# nlp_base.net
KiCad netlist of a schematic drawn in EasyEDA
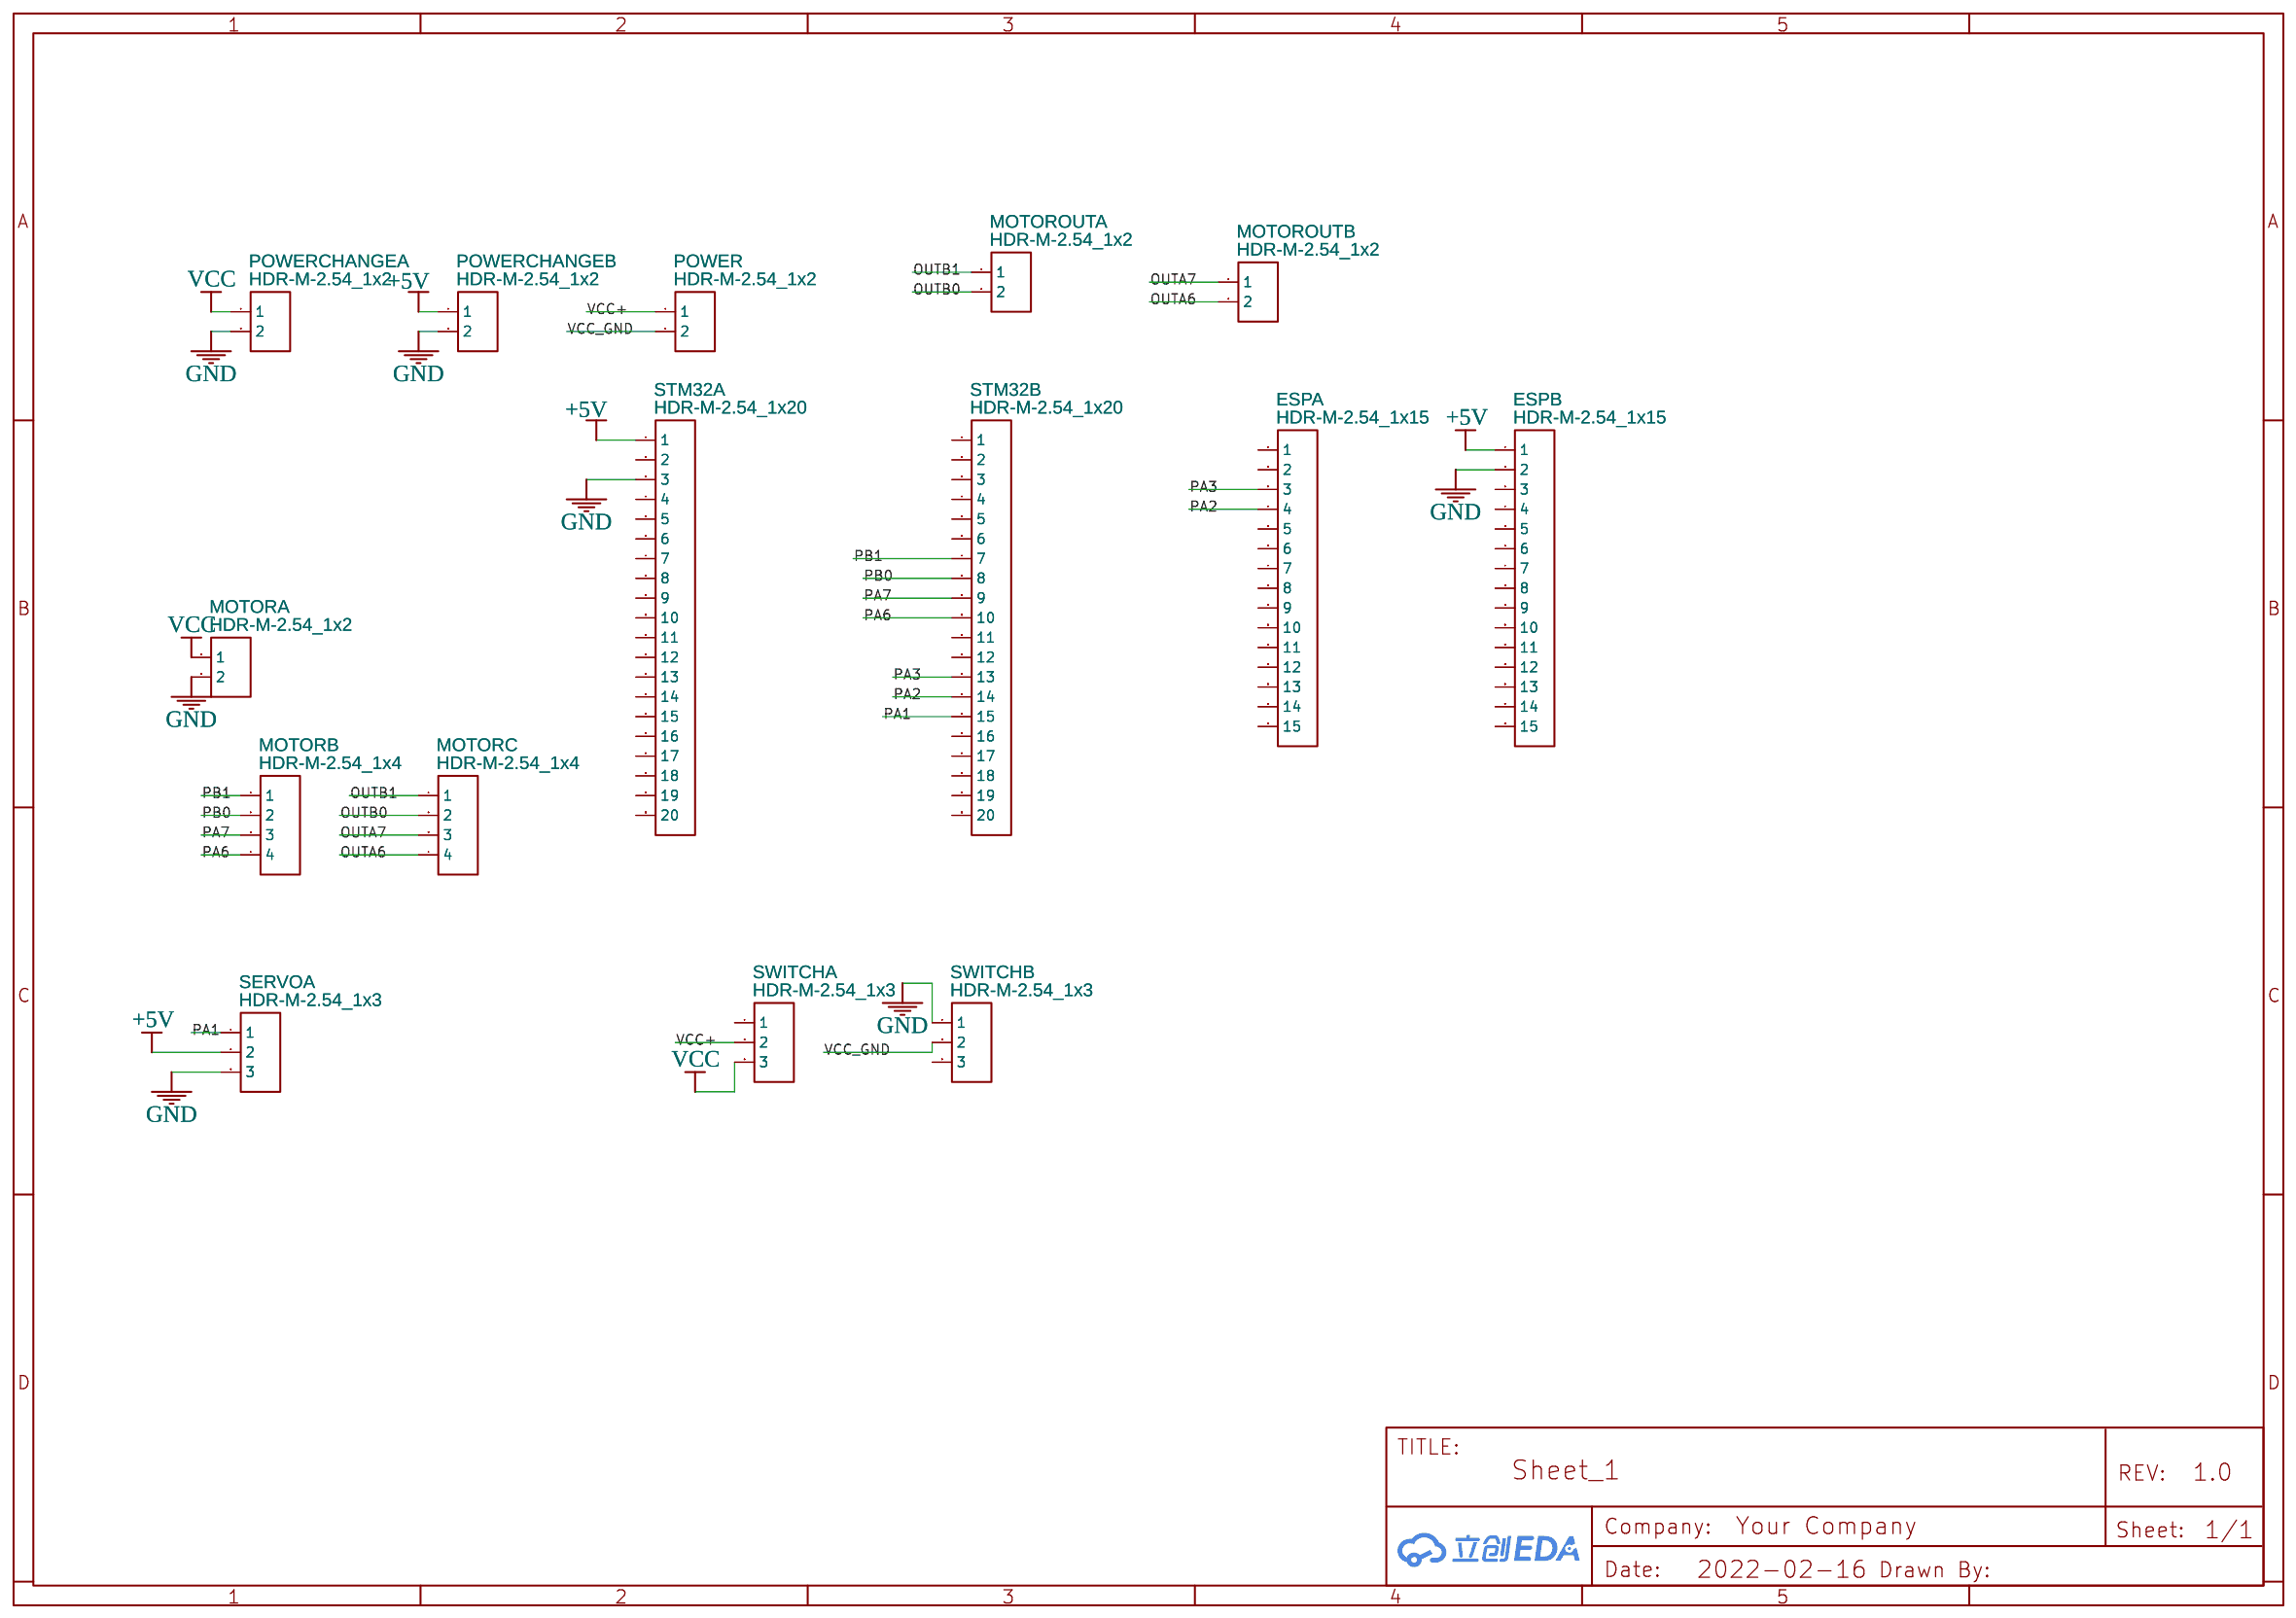
[diagram p0: schematic sheet]

(export (version "E")
  (design (tool "Eeschema 10.0.6"))
  (components
    (comp (ref "ESPA")
      (value "HDR-M-2.54_1x15")
      (fields (field (name "BOM_Supplier Part") "C124373"))
      (libsource (lib "") (part "HDR-M-2.54_1x15_1"))
    )
    (comp (ref "ESPB")
      (value "HDR-M-2.54_1x15")
      (fields (field (name "BOM_Supplier Part") "C124373"))
      (libsource (lib "") (part "HDR-M-2.54_1x15"))
    )
    (comp (ref "MOTORA")
      (value "HDR-M-2.54_1x2")
      (fields (field (name "BOM_Supplier Part") "C124375"))
      (libsource (lib "") (part "HDR-M-2.54_1x2_1"))
    )
    (comp (ref "MOTORB")
      (value "HDR-M-2.54_1x4")
      (fields (field (name "BOM_Supplier Part") "C124378"))
      (libsource (lib "") (part "HDR-M-2.54_1x4_1"))
    )
    (comp (ref "MOTORC")
      (value "HDR-M-2.54_1x4")
      (fields (field (name "BOM_Supplier Part") "C124378"))
      (libsource (lib "") (part "HDR-M-2.54_1x4"))
    )
    (comp (ref "MOTOROUTA")
      (value "HDR-M-2.54_1x2")
      (fields (field (name "BOM_Supplier Part") "C124375"))
      (libsource (lib "") (part "HDR-M-2.54_1x2_3"))
    )
    (comp (ref "MOTOROUTB")
      (value "HDR-M-2.54_1x2")
      (fields (field (name "BOM_Supplier Part") "C124375"))
      (libsource (lib "") (part "HDR-M-2.54_1x2_4"))
    )
    (comp (ref "POWER")
      (value "HDR-M-2.54_1x2")
      (fields (field (name "BOM_Supplier Part") "C124375"))
      (libsource (lib "") (part "HDR-M-2.54_1x2_2"))
    )
    (comp (ref "POWERCHANGEA")
      (value "HDR-M-2.54_1x2")
      (fields (field (name "BOM_Supplier Part") "C124375"))
      (libsource (lib "") (part "HDR-M-2.54_1x2"))
    )
    (comp (ref "POWERCHANGEB")
      (value "HDR-M-2.54_1x2")
      (fields (field (name "BOM_Supplier Part") "C124375"))
      (libsource (lib "") (part "HDR-M-2.54_1x2_5"))
    )
    (comp (ref "SERVOA")
      (value "HDR-M-2.54_1x3")
      (fields (field (name "BOM_Supplier Part") "C180248"))
      (libsource (lib "") (part "HDR-M-2.54_1x3_2"))
    )
    (comp (ref "STM32A")
      (value "HDR-M-2.54_1x20")
      (fields (field (name "BOM_Supplier Part") "C50981"))
      (libsource (lib "") (part "HDR-M-2.54_1x20_1"))
    )
    (comp (ref "STM32B")
      (value "HDR-M-2.54_1x20")
      (fields (field (name "BOM_Supplier Part") "C50981"))
      (libsource (lib "") (part "HDR-M-2.54_1x20"))
    )
    (comp (ref "SWITCHA")
      (value "HDR-M-2.54_1x3")
      (fields (field (name "BOM_Supplier Part") "C180248"))
      (libsource (lib "") (part "HDR-M-2.54_1x3_1"))
    )
    (comp (ref "SWITCHB")
      (value "HDR-M-2.54_1x3")
      (fields (field (name "BOM_Supplier Part") "C180248"))
      (libsource (lib "") (part "HDR-M-2.54_1x3"))
    )
  )
  (nets
    (net (code "1") (name "+5V") (class "Default")
      (node (ref "ESPB") (pin "1") (pinfunction "1_1") (pintype "unspecified"))
      (node (ref "POWERCHANGEB") (pin "1") (pinfunction "1_1") (pintype "unspecified"))
      (node (ref "SERVOA") (pin "2") (pinfunction "2_2") (pintype "input"))
      (node (ref "STM32A") (pin "1") (pinfunction "1_1") (pintype "unspecified"))
    )
    (net (code "2") (name "/OUTA6") (class "Default")
      (node (ref "MOTORC") (pin "4") (pinfunction "4_4") (pintype "unspecified"))
      (node (ref "MOTOROUTB") (pin "2") (pinfunction "2_2") (pintype "unspecified"))
    )
    (net (code "3") (name "/OUTA7") (class "Default")
      (node (ref "MOTORC") (pin "3") (pinfunction "3_3") (pintype "unspecified"))
      (node (ref "MOTOROUTB") (pin "1") (pinfunction "1_1") (pintype "unspecified"))
    )
    (net (code "4") (name "/OUTB0") (class "Default")
      (node (ref "MOTORC") (pin "2") (pinfunction "2_2") (pintype "unspecified"))
      (node (ref "MOTOROUTA") (pin "2") (pinfunction "2_2") (pintype "unspecified"))
    )
    (net (code "5") (name "/OUTB1") (class "Default")
      (node (ref "MOTORC") (pin "1") (pinfunction "1_1") (pintype "unspecified"))
      (node (ref "MOTOROUTA") (pin "1") (pinfunction "1_1") (pintype "unspecified"))
    )
    (net (code "6") (name "/PA1") (class "Default")
      (node (ref "SERVOA") (pin "1") (pinfunction "1_1") (pintype "input"))
      (node (ref "STM32B") (pin "15") (pinfunction "15_15") (pintype "unspecified"))
    )
    (net (code "7") (name "/PA2") (class "Default")
      (node (ref "ESPA") (pin "4") (pinfunction "4_4") (pintype "unspecified"))
      (node (ref "STM32B") (pin "14") (pinfunction "14_14") (pintype "unspecified"))
    )
    (net (code "8") (name "/PA3") (class "Default")
      (node (ref "ESPA") (pin "3") (pinfunction "3_3") (pintype "unspecified"))
      (node (ref "STM32B") (pin "13") (pinfunction "13_13") (pintype "unspecified"))
    )
    (net (code "9") (name "/PA6") (class "Default")
      (node (ref "MOTORB") (pin "4") (pinfunction "4_4") (pintype "unspecified"))
      (node (ref "STM32B") (pin "10") (pinfunction "10_10") (pintype "unspecified"))
    )
    (net (code "10") (name "/PA7") (class "Default")
      (node (ref "MOTORB") (pin "3") (pinfunction "3_3") (pintype "unspecified"))
      (node (ref "STM32B") (pin "9") (pinfunction "9_9") (pintype "unspecified"))
    )
    (net (code "11") (name "/PB0") (class "Default")
      (node (ref "MOTORB") (pin "2") (pinfunction "2_2") (pintype "unspecified"))
      (node (ref "STM32B") (pin "8") (pinfunction "8_8") (pintype "unspecified"))
    )
    (net (code "12") (name "/PB1") (class "Default")
      (node (ref "MOTORB") (pin "1") (pinfunction "1_1") (pintype "unspecified"))
      (node (ref "STM32B") (pin "7") (pinfunction "7_7") (pintype "unspecified"))
    )
    (net (code "13") (name "/VCC+") (class "Default")
      (node (ref "POWER") (pin "1") (pinfunction "1_1") (pintype "unspecified"))
      (node (ref "SWITCHA") (pin "2") (pinfunction "2_2") (pintype "input"))
    )
    (net (code "14") (name "/VCC_GND") (class "Default")
      (node (ref "POWER") (pin "2") (pinfunction "2_2") (pintype "unspecified"))
      (node (ref "SWITCHB") (pin "2") (pinfunction "2_2") (pintype "input"))
    )
    (net (code "15") (name "GND") (class "Default")
      (node (ref "ESPB") (pin "2") (pinfunction "2_2") (pintype "unspecified"))
      (node (ref "MOTORA") (pin "2") (pinfunction "2_2") (pintype "unspecified"))
      (node (ref "POWERCHANGEA") (pin "2") (pinfunction "2_2") (pintype "unspecified"))
      (node (ref "POWERCHANGEB") (pin "2") (pinfunction "2_2") (pintype "unspecified"))
      (node (ref "SERVOA") (pin "3") (pinfunction "3_3") (pintype "input"))
      (node (ref "STM32A") (pin "3") (pinfunction "3_3") (pintype "unspecified"))
      (node (ref "SWITCHB") (pin "1") (pinfunction "1_1") (pintype "input"))
    )
    (net (code "16") (name "VCC") (class "Default")
      (node (ref "MOTORA") (pin "1") (pinfunction "1_1") (pintype "unspecified"))
      (node (ref "POWERCHANGEA") (pin "1") (pinfunction "1_1") (pintype "unspecified"))
      (node (ref "SWITCHA") (pin "3") (pinfunction "3_3") (pintype "input"))
    )
    (net (code "17") (name "unconnected-(ESPA-Pad1)") (class "Default")
      (node (ref "ESPA") (pin "1") (pinfunction "1_1") (pintype "unspecified"))
    )
    (net (code "18") (name "unconnected-(ESPA-Pad2)") (class "Default")
      (node (ref "ESPA") (pin "2") (pinfunction "2_2") (pintype "unspecified"))
    )
    (net (code "19") (name "unconnected-(ESPA-Pad5)") (class "Default")
      (node (ref "ESPA") (pin "5") (pinfunction "5_5") (pintype "unspecified"))
    )
    (net (code "20") (name "unconnected-(ESPA-Pad6)") (class "Default")
      (node (ref "ESPA") (pin "6") (pinfunction "6_6") (pintype "unspecified"))
    )
    (net (code "21") (name "unconnected-(ESPA-Pad7)") (class "Default")
      (node (ref "ESPA") (pin "7") (pinfunction "7_7") (pintype "unspecified"))
    )
    (net (code "22") (name "unconnected-(ESPA-Pad8)") (class "Default")
      (node (ref "ESPA") (pin "8") (pinfunction "8_8") (pintype "unspecified"))
    )
    (net (code "23") (name "unconnected-(ESPA-Pad9)") (class "Default")
      (node (ref "ESPA") (pin "9") (pinfunction "9_9") (pintype "unspecified"))
    )
    (net (code "24") (name "unconnected-(ESPA-Pad10)") (class "Default")
      (node (ref "ESPA") (pin "10") (pinfunction "10_10") (pintype "unspecified"))
    )
    (net (code "25") (name "unconnected-(ESPA-Pad11)") (class "Default")
      (node (ref "ESPA") (pin "11") (pinfunction "11_11") (pintype "unspecified"))
    )
    (net (code "26") (name "unconnected-(ESPA-Pad12)") (class "Default")
      (node (ref "ESPA") (pin "12") (pinfunction "12_12") (pintype "unspecified"))
    )
    (net (code "27") (name "unconnected-(ESPA-Pad13)") (class "Default")
      (node (ref "ESPA") (pin "13") (pinfunction "13_13") (pintype "unspecified"))
    )
    (net (code "28") (name "unconnected-(ESPA-Pad14)") (class "Default")
      (node (ref "ESPA") (pin "14") (pinfunction "14_14") (pintype "unspecified"))
    )
    (net (code "29") (name "unconnected-(ESPA-Pad15)") (class "Default")
      (node (ref "ESPA") (pin "15") (pinfunction "15_15") (pintype "unspecified"))
    )
    (net (code "30") (name "unconnected-(ESPB-Pad3)") (class "Default")
      (node (ref "ESPB") (pin "3") (pinfunction "3_3") (pintype "unspecified"))
    )
    (net (code "31") (name "unconnected-(ESPB-Pad4)") (class "Default")
      (node (ref "ESPB") (pin "4") (pinfunction "4_4") (pintype "unspecified"))
    )
    (net (code "32") (name "unconnected-(ESPB-Pad5)") (class "Default")
      (node (ref "ESPB") (pin "5") (pinfunction "5_5") (pintype "unspecified"))
    )
    (net (code "33") (name "unconnected-(ESPB-Pad6)") (class "Default")
      (node (ref "ESPB") (pin "6") (pinfunction "6_6") (pintype "unspecified"))
    )
    (net (code "34") (name "unconnected-(ESPB-Pad7)") (class "Default")
      (node (ref "ESPB") (pin "7") (pinfunction "7_7") (pintype "unspecified"))
    )
    (net (code "35") (name "unconnected-(ESPB-Pad8)") (class "Default")
      (node (ref "ESPB") (pin "8") (pinfunction "8_8") (pintype "unspecified"))
    )
    (net (code "36") (name "unconnected-(ESPB-Pad9)") (class "Default")
      (node (ref "ESPB") (pin "9") (pinfunction "9_9") (pintype "unspecified"))
    )
    (net (code "37") (name "unconnected-(ESPB-Pad10)") (class "Default")
      (node (ref "ESPB") (pin "10") (pinfunction "10_10") (pintype "unspecified"))
    )
    (net (code "38") (name "unconnected-(ESPB-Pad11)") (class "Default")
      (node (ref "ESPB") (pin "11") (pinfunction "11_11") (pintype "unspecified"))
    )
    (net (code "39") (name "unconnected-(ESPB-Pad12)") (class "Default")
      (node (ref "ESPB") (pin "12") (pinfunction "12_12") (pintype "unspecified"))
    )
    (net (code "40") (name "unconnected-(ESPB-Pad13)") (class "Default")
      (node (ref "ESPB") (pin "13") (pinfunction "13_13") (pintype "unspecified"))
    )
    (net (code "41") (name "unconnected-(ESPB-Pad14)") (class "Default")
      (node (ref "ESPB") (pin "14") (pinfunction "14_14") (pintype "unspecified"))
    )
    (net (code "42") (name "unconnected-(ESPB-Pad15)") (class "Default")
      (node (ref "ESPB") (pin "15") (pinfunction "15_15") (pintype "unspecified"))
    )
    (net (code "43") (name "unconnected-(STM32A-Pad2)") (class "Default")
      (node (ref "STM32A") (pin "2") (pinfunction "2_2") (pintype "unspecified"))
    )
    (net (code "44") (name "unconnected-(STM32A-Pad4)") (class "Default")
      (node (ref "STM32A") (pin "4") (pinfunction "4_4") (pintype "unspecified"))
    )
    (net (code "45") (name "unconnected-(STM32A-Pad5)") (class "Default")
      (node (ref "STM32A") (pin "5") (pinfunction "5_5") (pintype "unspecified"))
    )
    (net (code "46") (name "unconnected-(STM32A-Pad6)") (class "Default")
      (node (ref "STM32A") (pin "6") (pinfunction "6_6") (pintype "unspecified"))
    )
    (net (code "47") (name "unconnected-(STM32A-Pad7)") (class "Default")
      (node (ref "STM32A") (pin "7") (pinfunction "7_7") (pintype "unspecified"))
    )
    (net (code "48") (name "unconnected-(STM32A-Pad8)") (class "Default")
      (node (ref "STM32A") (pin "8") (pinfunction "8_8") (pintype "unspecified"))
    )
    (net (code "49") (name "unconnected-(STM32A-Pad9)") (class "Default")
      (node (ref "STM32A") (pin "9") (pinfunction "9_9") (pintype "unspecified"))
    )
    (net (code "50") (name "unconnected-(STM32A-Pad10)") (class "Default")
      (node (ref "STM32A") (pin "10") (pinfunction "10_10") (pintype "unspecified"))
    )
    (net (code "51") (name "unconnected-(STM32A-Pad11)") (class "Default")
      (node (ref "STM32A") (pin "11") (pinfunction "11_11") (pintype "unspecified"))
    )
    (net (code "52") (name "unconnected-(STM32A-Pad12)") (class "Default")
      (node (ref "STM32A") (pin "12") (pinfunction "12_12") (pintype "unspecified"))
    )
    (net (code "53") (name "unconnected-(STM32A-Pad13)") (class "Default")
      (node (ref "STM32A") (pin "13") (pinfunction "13_13") (pintype "unspecified"))
    )
    (net (code "54") (name "unconnected-(STM32A-Pad14)") (class "Default")
      (node (ref "STM32A") (pin "14") (pinfunction "14_14") (pintype "unspecified"))
    )
    (net (code "55") (name "unconnected-(STM32A-Pad15)") (class "Default")
      (node (ref "STM32A") (pin "15") (pinfunction "15_15") (pintype "unspecified"))
    )
    (net (code "56") (name "unconnected-(STM32A-Pad16)") (class "Default")
      (node (ref "STM32A") (pin "16") (pinfunction "16_16") (pintype "unspecified"))
    )
    (net (code "57") (name "unconnected-(STM32A-Pad17)") (class "Default")
      (node (ref "STM32A") (pin "17") (pinfunction "17_17") (pintype "unspecified"))
    )
    (net (code "58") (name "unconnected-(STM32A-Pad18)") (class "Default")
      (node (ref "STM32A") (pin "18") (pinfunction "18_18") (pintype "unspecified"))
    )
    (net (code "59") (name "unconnected-(STM32A-Pad19)") (class "Default")
      (node (ref "STM32A") (pin "19") (pinfunction "19_19") (pintype "unspecified"))
    )
    (net (code "60") (name "unconnected-(STM32A-Pad20)") (class "Default")
      (node (ref "STM32A") (pin "20") (pinfunction "20_20") (pintype "unspecified"))
    )
    (net (code "61") (name "unconnected-(STM32B-Pad1)") (class "Default")
      (node (ref "STM32B") (pin "1") (pinfunction "1_1") (pintype "unspecified"))
    )
    (net (code "62") (name "unconnected-(STM32B-Pad2)") (class "Default")
      (node (ref "STM32B") (pin "2") (pinfunction "2_2") (pintype "unspecified"))
    )
    (net (code "63") (name "unconnected-(STM32B-Pad3)") (class "Default")
      (node (ref "STM32B") (pin "3") (pinfunction "3_3") (pintype "unspecified"))
    )
    (net (code "64") (name "unconnected-(STM32B-Pad4)") (class "Default")
      (node (ref "STM32B") (pin "4") (pinfunction "4_4") (pintype "unspecified"))
    )
    (net (code "65") (name "unconnected-(STM32B-Pad5)") (class "Default")
      (node (ref "STM32B") (pin "5") (pinfunction "5_5") (pintype "unspecified"))
    )
    (net (code "66") (name "unconnected-(STM32B-Pad6)") (class "Default")
      (node (ref "STM32B") (pin "6") (pinfunction "6_6") (pintype "unspecified"))
    )
    (net (code "67") (name "unconnected-(STM32B-Pad11)") (class "Default")
      (node (ref "STM32B") (pin "11") (pinfunction "11_11") (pintype "unspecified"))
    )
    (net (code "68") (name "unconnected-(STM32B-Pad12)") (class "Default")
      (node (ref "STM32B") (pin "12") (pinfunction "12_12") (pintype "unspecified"))
    )
    (net (code "69") (name "unconnected-(STM32B-Pad16)") (class "Default")
      (node (ref "STM32B") (pin "16") (pinfunction "16_16") (pintype "unspecified"))
    )
    (net (code "70") (name "unconnected-(STM32B-Pad17)") (class "Default")
      (node (ref "STM32B") (pin "17") (pinfunction "17_17") (pintype "unspecified"))
    )
    (net (code "71") (name "unconnected-(STM32B-Pad18)") (class "Default")
      (node (ref "STM32B") (pin "18") (pinfunction "18_18") (pintype "unspecified"))
    )
    (net (code "72") (name "unconnected-(STM32B-Pad19)") (class "Default")
      (node (ref "STM32B") (pin "19") (pinfunction "19_19") (pintype "unspecified"))
    )
    (net (code "73") (name "unconnected-(STM32B-Pad20)") (class "Default")
      (node (ref "STM32B") (pin "20") (pinfunction "20_20") (pintype "unspecified"))
    )
    (net (code "74") (name "unconnected-(SWITCHA-Pad1)") (class "Default")
      (node (ref "SWITCHA") (pin "1") (pinfunction "1_1") (pintype "input"))
    )
    (net (code "75") (name "unconnected-(SWITCHB-Pad3)") (class "Default")
      (node (ref "SWITCHB") (pin "3") (pinfunction "3_3") (pintype "input"))
    )
  )
)
